# Breadboard_Power_Supply_-_3_3-1_8SMD.net
KiCad netlist of a schematic drawn in EAGLE
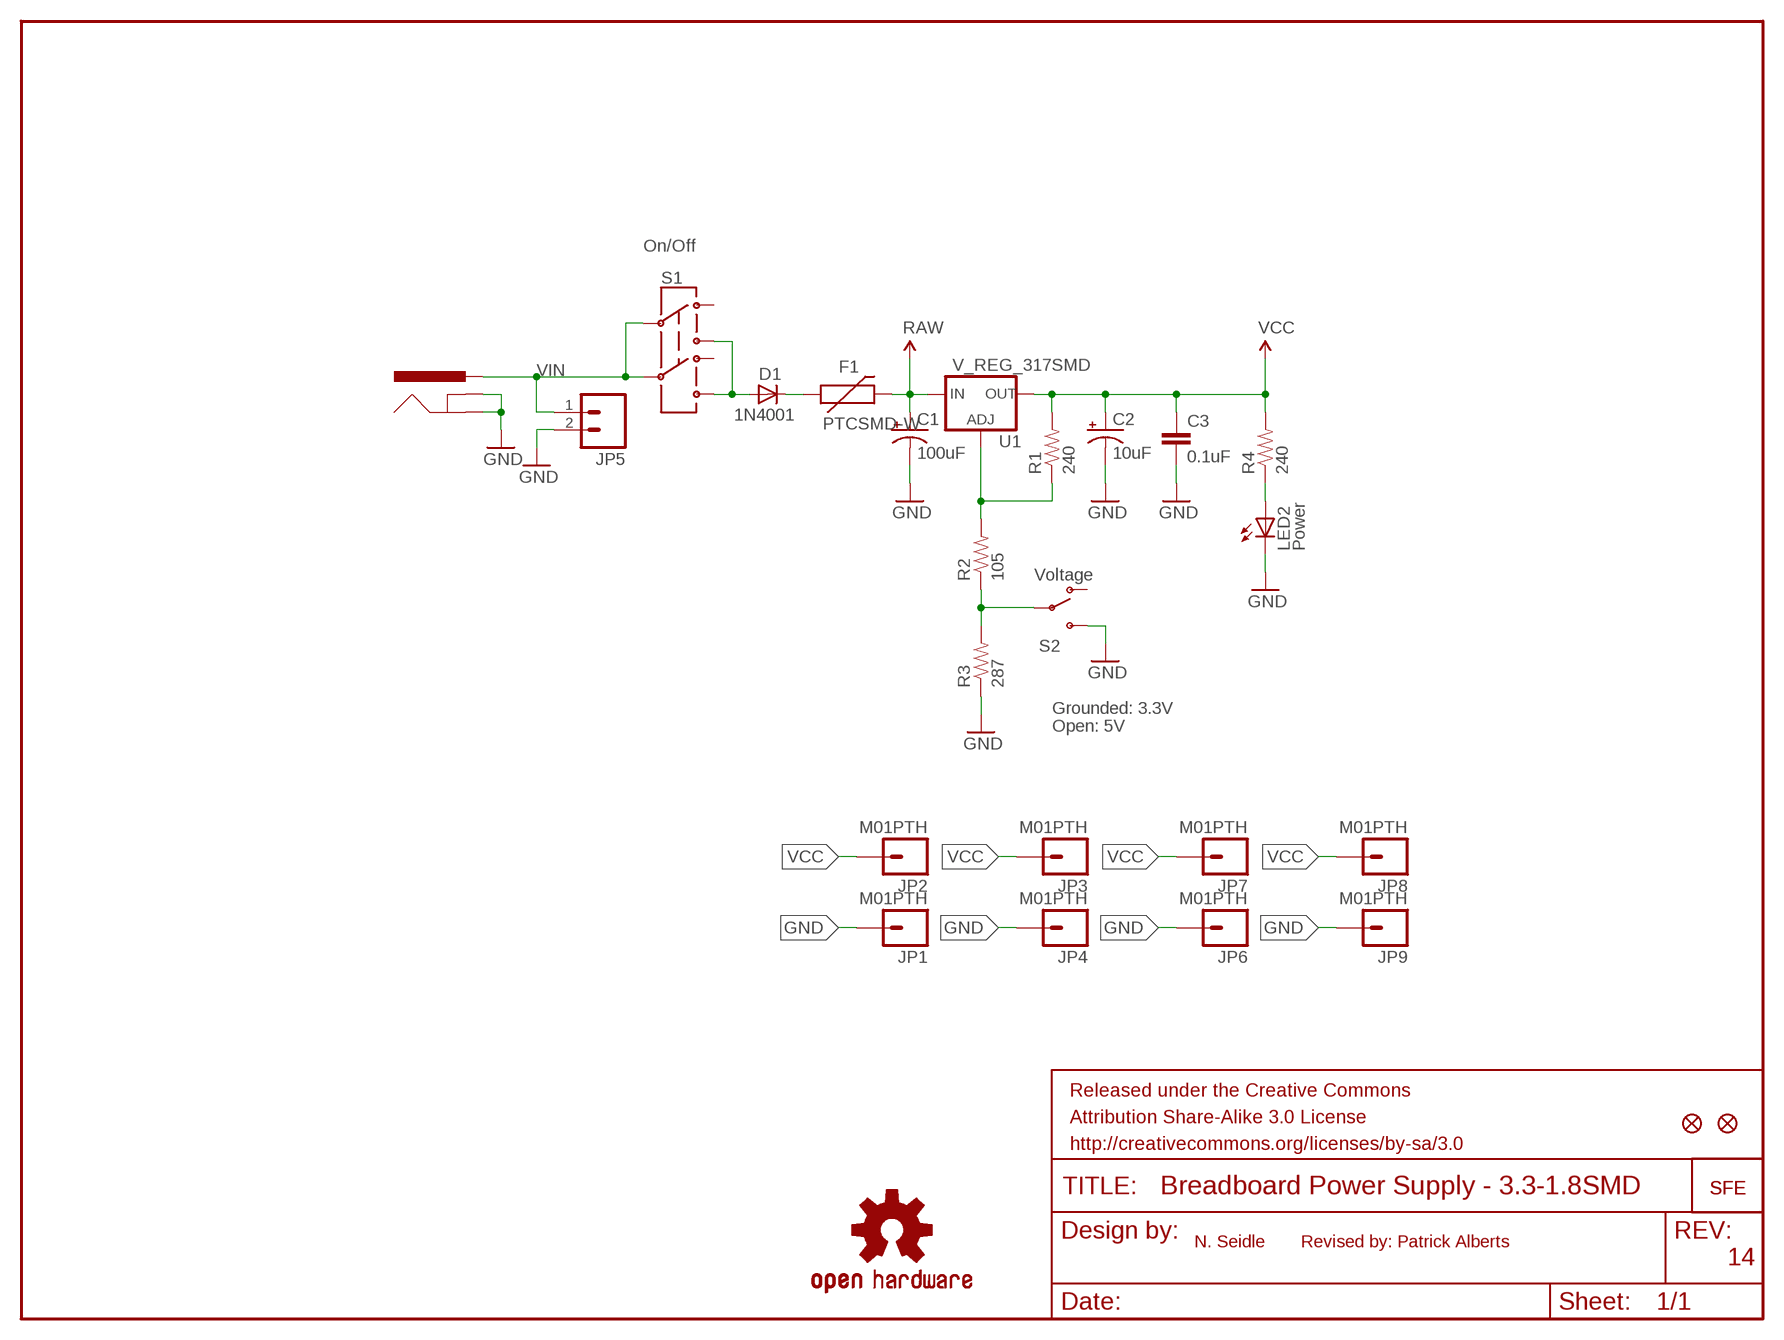
[diagram p0: schematic, sheet 1]

(export (version "E")
  (design (tool "Eeschema 10.0.6"))
  (components
    (comp (ref "C1")
      (value "100uF")
      (footprint "eagle-import:EIA7343")
      (libsource (lib "eagle-import") (part "CAP_POL7343"))
    )
    (comp (ref "C2")
      (value "10uF")
      (footprint "eagle-import:EIA3216")
      (libsource (lib "eagle-import") (part "CAP_POL1206"))
    )
    (comp (ref "C3")
      (value "0.1uF")
      (footprint "eagle-import:0603-CAP")
      (libsource (lib "eagle-import") (part "CAP0603-CAP"))
    )
    (comp (ref "D1")
      (value "1N4001")
      (footprint "eagle-import:SMA-DIODE-TYLERALT1")
      (libsource (lib "eagle-import") (part "DIODESMA-TYLERALT1"))
    )
    (comp (ref "F1")
      (value "PTCSMD-W")
      (footprint "eagle-import:PTC-1206-WIDE")
      (libsource (lib "eagle-import") (part "PTCSMD-W"))
    )
    (comp (ref "FRAME1")
      (value "FRAME-LETTER")
      (footprint "eagle-import:CREATIVE_COMMONS")
      (libsource (lib "eagle-import") (part "FRAME-LETTER"))
    )
    (comp (ref "J1")
      (value "POWER_JACKOVERPASTE_REDBOARD_0603")
      (footprint "eagle-import:POWER_JACK_SMD_OVERPASTE_REDBOARD_0603")
      (libsource (lib "eagle-import") (part "POWER_JACKOVERPASTE_REDBOARD_0603"))
    )
    (comp (ref "JP1")
      (value "M01PTH")
      (footprint "eagle-import:1X01")
      (libsource (lib "eagle-import") (part "M01PTH"))
    )
    (comp (ref "JP2")
      (value "M01PTH")
      (footprint "eagle-import:1X01")
      (libsource (lib "eagle-import") (part "M01PTH"))
    )
    (comp (ref "JP3")
      (value "M01PTH")
      (footprint "eagle-import:1X01")
      (libsource (lib "eagle-import") (part "M01PTH"))
    )
    (comp (ref "JP4")
      (value "M01PTH")
      (footprint "eagle-import:1X01")
      (libsource (lib "eagle-import") (part "M01PTH"))
    )
    (comp (ref "JP5")
      (value "M02PTH")
      (footprint "eagle-import:1X02")
      (libsource (lib "eagle-import") (part "M02PTH"))
    )
    (comp (ref "JP6")
      (value "M01PTH")
      (footprint "eagle-import:1X01")
      (libsource (lib "eagle-import") (part "M01PTH"))
    )
    (comp (ref "JP7")
      (value "M01PTH")
      (footprint "eagle-import:1X01")
      (libsource (lib "eagle-import") (part "M01PTH"))
    )
    (comp (ref "JP8")
      (value "M01PTH")
      (footprint "eagle-import:1X01")
      (libsource (lib "eagle-import") (part "M01PTH"))
    )
    (comp (ref "JP9")
      (value "M01PTH")
      (footprint "eagle-import:1X01")
      (libsource (lib "eagle-import") (part "M01PTH"))
    )
    (comp (ref "LED2")
      (value "Power")
      (footprint "eagle-import:LED-1206")
      (libsource (lib "eagle-import") (part "LED1206"))
    )
    (comp (ref "LOGO1")
      (value "OSHW-LOGOS")
      (footprint "eagle-import:OSHW-LOGO-S")
      (libsource (lib "eagle-import") (part "OSHW-LOGOS"))
    )
    (comp (ref "R1")
      (value "240")
      (footprint "eagle-import:0603-RES")
      (libsource (lib "eagle-import") (part "240OHM1/10W1%(0603)"))
    )
    (comp (ref "R2")
      (value "105")
      (footprint "eagle-import:0603-RES")
      (libsource (lib "eagle-import") (part "105OHM-1/10W-1%(0603)"))
    )
    (comp (ref "R3")
      (value "287")
      (footprint "eagle-import:0603-RES")
      (libsource (lib "eagle-import") (part "287OHM-1/10W-1%(0603)"))
    )
    (comp (ref "R4")
      (value "240")
      (footprint "eagle-import:0603-RES")
      (libsource (lib "eagle-import") (part "240OHM1/10W1%(0603)"))
    )
    (comp (ref "S1")
      (value "On/Off")
      (footprint "eagle-import:AYZ0202")
      (libsource (lib "eagle-import") (part "AYZ0202"))
    )
    (comp (ref "S2")
      (value "Voltage")
      (footprint "eagle-import:AYZ0202")
      (libsource (lib "eagle-import") (part "SWITCH-SPSTSMD"))
    )
    (comp (ref "U$1")
      (value "LOGO-SFESK")
      (footprint "eagle-import:SFE-LOGO-FLAME")
      (libsource (lib "eagle-import") (part "LOGO-SFESK"))
    )
    (comp (ref "U$2")
      (value "LOGO-SFENEW")
      (footprint "eagle-import:SFE-NEW-WEBLOGO")
      (libsource (lib "eagle-import") (part "LOGO-SFENEW"))
    )
    (comp (ref "U$3")
      (value "FIDUCIAL1X2")
      (footprint "eagle-import:FIDUCIAL-1X2")
      (libsource (lib "eagle-import") (part "FIDUCIAL1X2"))
    )
    (comp (ref "U$4")
      (value "FIDUCIAL1X2")
      (footprint "eagle-import:FIDUCIAL-1X2")
      (libsource (lib "eagle-import") (part "FIDUCIAL1X2"))
    )
    (comp (ref "U1")
      (value "V_REG_317SMD")
      (footprint "eagle-import:SOT223")
      (libsource (lib "eagle-import") (part "V_REG_317SMD"))
    )
  )
  (nets
    (net (code "1") (name "/VIN") (class "Default")
      (node (ref "J1") (pin "VIN0") (pinfunction "PWR_VIN0") (pintype "bidirectional"))
      (node (ref "JP5") (pin "1") (pinfunction "1_1") (pintype "passive"))
      (node (ref "S1") (pin "2") (pinfunction "2_2") (pintype "bidirectional"))
      (node (ref "S1") (pin "5") (pinfunction "5_5") (pintype "bidirectional"))
    )
    (net (code "2") (name "GND") (class "Default")
      (node (ref "C1") (pin "C") (pinfunction "-_C") (pintype "passive"))
      (node (ref "C2") (pin "C") (pinfunction "-_C") (pintype "passive"))
      (node (ref "C3") (pin "2") (pinfunction "2_2") (pintype "passive"))
      (node (ref "J1") (pin "GND") (pinfunction "GNDBREAK_GND") (pintype "bidirectional"))
      (node (ref "J1") (pin "P$4") (pinfunction "GND_P$4") (pintype "bidirectional"))
      (node (ref "JP1") (pin "1") (pinfunction "1_1") (pintype "passive"))
      (node (ref "JP4") (pin "1") (pinfunction "1_1") (pintype "passive"))
      (node (ref "JP5") (pin "2") (pinfunction "2_2") (pintype "passive"))
      (node (ref "JP6") (pin "1") (pinfunction "1_1") (pintype "passive"))
      (node (ref "JP9") (pin "1") (pinfunction "1_1") (pintype "passive"))
      (node (ref "LED2") (pin "C") (pinfunction "C_C") (pintype "passive"))
      (node (ref "R3") (pin "1") (pinfunction "1_1") (pintype "passive"))
      (node (ref "S2") (pin "3") (pinfunction "S_3") (pintype "passive"))
    )
    (net (code "3") (name "Net-(D1-PadC)") (class "Default")
      (node (ref "D1") (pin "C") (pinfunction "C_C") (pintype "passive"))
      (node (ref "F1") (pin "1") (pinfunction "1_1") (pintype "bidirectional"))
    )
    (net (code "4") (name "Net-(LED2-PadA)") (class "Default")
      (node (ref "LED2") (pin "A") (pinfunction "A_A") (pintype "passive"))
      (node (ref "R4") (pin "1") (pinfunction "1_1") (pintype "passive"))
    )
    (net (code "5") (name "Net-(S1-3)") (class "Default")
      (node (ref "D1") (pin "A") (pinfunction "A_A") (pintype "passive"))
      (node (ref "S1") (pin "1") (pinfunction "3_1") (pintype "bidirectional"))
      (node (ref "S1") (pin "4") (pinfunction "6_4") (pintype "bidirectional"))
    )
    (net (code "6") (name "Net-(S2-P)") (class "Default")
      (node (ref "R2") (pin "1") (pinfunction "1_1") (pintype "passive"))
      (node (ref "R3") (pin "2") (pinfunction "2_2") (pintype "passive"))
      (node (ref "S2") (pin "2") (pinfunction "P_2") (pintype "passive"))
    )
    (net (code "7") (name "Net-(U1-ADJ)") (class "Default")
      (node (ref "R1") (pin "1") (pinfunction "1_1") (pintype "passive"))
      (node (ref "R2") (pin "2") (pinfunction "2_2") (pintype "passive"))
      (node (ref "U1") (pin "1") (pinfunction "ADJ_1") (pintype "input"))
    )
    (net (code "8") (name "RAW") (class "Default")
      (node (ref "C1") (pin "A") (pinfunction "+_A") (pintype "passive"))
      (node (ref "F1") (pin "2") (pinfunction "2_2") (pintype "bidirectional"))
      (node (ref "U1") (pin "3") (pinfunction "IN_3") (pintype "input"))
    )
    (net (code "9") (name "VCC") (class "Default")
      (node (ref "C2") (pin "A") (pinfunction "+_A") (pintype "passive"))
      (node (ref "C3") (pin "1") (pinfunction "1_1") (pintype "passive"))
      (node (ref "JP2") (pin "1") (pinfunction "1_1") (pintype "passive"))
      (node (ref "JP3") (pin "1") (pinfunction "1_1") (pintype "passive"))
      (node (ref "JP7") (pin "1") (pinfunction "1_1") (pintype "passive"))
      (node (ref "JP8") (pin "1") (pinfunction "1_1") (pintype "passive"))
      (node (ref "R1") (pin "2") (pinfunction "2_2") (pintype "passive"))
      (node (ref "R4") (pin "2") (pinfunction "2_2") (pintype "passive"))
      (node (ref "U1") (pin "2") (pinfunction "OUT_2") (pintype "output"))
    )
    (net (code "10") (name "unconnected-(S1-1-Pad3)") (class "Default")
      (node (ref "S1") (pin "3") (pinfunction "1_3") (pintype "bidirectional"))
    )
    (net (code "11") (name "unconnected-(S1-4-Pad6)") (class "Default")
      (node (ref "S1") (pin "6") (pinfunction "4_6") (pintype "bidirectional"))
    )
    (net (code "12") (name "unconnected-(S2-O-Pad1)") (class "Default")
      (node (ref "S2") (pin "1") (pinfunction "O_1") (pintype "passive"))
    )
  )
)
